# Arc.net
KiCad netlist of a schematic drawn in Altium Designer
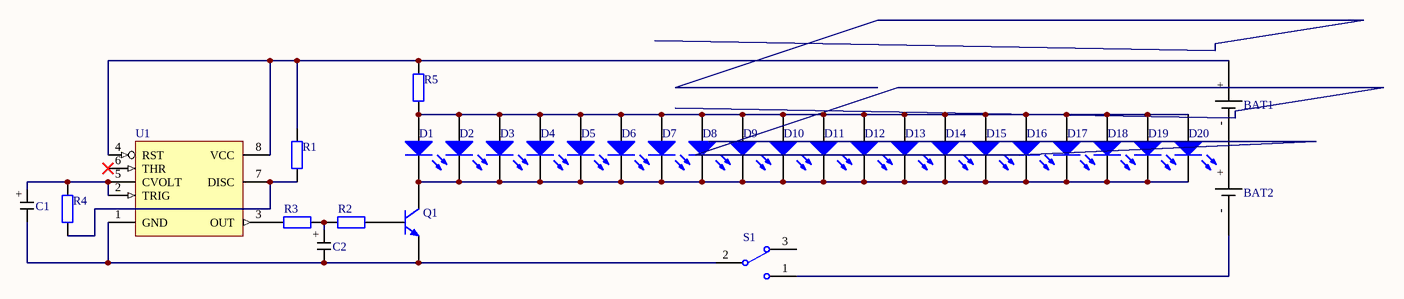
[diagram p0: Arc.SchDoc]

(export (version "E")
  (design (tool "Eeschema 10.0.6"))
  (components
    (comp (ref "BAT1") (value "Power") (footprint "CR1220_Dock") (libsource (lib "Powerlib") (part "Power")))
    (comp (ref "BAT2") (value "Power") (footprint "CR1220_Dock") (libsource (lib "Powerlib") (part "Power")))
    (comp (ref "C1") (value "Cap") (footprint "*CAPCP3528X210N") (libsource (lib "Powerlib") (part "Cap")))
    (comp (ref "C2") (value "Cap") (footprint "*CAPCP3528X210N") (libsource (lib "Powerlib") (part "Cap")))
    (comp (ref "D1")
      (value "蓝灯 0603")
      (footprint "0603_LED_S1")
      (description "发光二极管")
      (libsource (lib "Miscellaneous Devices LC") (part "0603 蓝灯"))
    )
    (comp (ref "D2")
      (value "蓝灯 0603")
      (footprint "0603_LED_S1")
      (description "发光二极管")
      (libsource (lib "Miscellaneous Devices LC") (part "0603 蓝灯"))
    )
    (comp (ref "D3")
      (value "蓝灯 0603")
      (footprint "0603_LED_S1")
      (description "发光二极管")
      (libsource (lib "Miscellaneous Devices LC") (part "0603 蓝灯"))
    )
    (comp (ref "D4")
      (value "蓝灯 0603")
      (footprint "0603_LED_S1")
      (description "发光二极管")
      (libsource (lib "Miscellaneous Devices LC") (part "0603 蓝灯"))
    )
    (comp (ref "D5")
      (value "蓝灯 0603")
      (footprint "0603_LED_S1")
      (description "发光二极管")
      (libsource (lib "Miscellaneous Devices LC") (part "0603 蓝灯"))
    )
    (comp (ref "D6")
      (value "蓝灯 0603")
      (footprint "0603_LED_S1")
      (description "发光二极管")
      (libsource (lib "Miscellaneous Devices LC") (part "0603 蓝灯"))
    )
    (comp (ref "D7")
      (value "蓝灯 0603")
      (footprint "0603_LED_S1")
      (description "发光二极管")
      (libsource (lib "Miscellaneous Devices LC") (part "0603 蓝灯"))
    )
    (comp (ref "D8")
      (value "蓝灯 0603")
      (footprint "0603_LED_S1")
      (description "发光二极管")
      (libsource (lib "Miscellaneous Devices LC") (part "0603 蓝灯"))
    )
    (comp (ref "D9")
      (value "蓝灯 0603")
      (footprint "0603_LED_S1")
      (description "发光二极管")
      (libsource (lib "Miscellaneous Devices LC") (part "0603 蓝灯"))
    )
    (comp (ref "D10")
      (value "蓝灯 0603")
      (footprint "0603_LED_S1")
      (description "发光二极管")
      (libsource (lib "Miscellaneous Devices LC") (part "0603 蓝灯"))
    )
    (comp (ref "D11")
      (value "蓝灯 0603")
      (footprint "0603_LED_S1")
      (description "发光二极管")
      (libsource (lib "Miscellaneous Devices LC") (part "0603 蓝灯"))
    )
    (comp (ref "D12")
      (value "蓝灯 0603")
      (footprint "0603_LED_S1")
      (description "发光二极管")
      (libsource (lib "Miscellaneous Devices LC") (part "0603 蓝灯"))
    )
    (comp (ref "D13")
      (value "蓝灯 0603")
      (footprint "0603_LED_S1")
      (description "发光二极管")
      (libsource (lib "Miscellaneous Devices LC") (part "0603 蓝灯"))
    )
    (comp (ref "D14")
      (value "蓝灯 0603")
      (footprint "0603_LED_S1")
      (description "发光二极管")
      (libsource (lib "Miscellaneous Devices LC") (part "0603 蓝灯"))
    )
    (comp (ref "D15")
      (value "蓝灯 0603")
      (footprint "0603_LED_S1")
      (description "发光二极管")
      (libsource (lib "Miscellaneous Devices LC") (part "0603 蓝灯"))
    )
    (comp (ref "D16")
      (value "蓝灯 0603")
      (footprint "0603_LED_S1")
      (description "发光二极管")
      (libsource (lib "Miscellaneous Devices LC") (part "0603 蓝灯"))
    )
    (comp (ref "D17")
      (value "蓝灯 0603")
      (footprint "0603_LED_S1")
      (description "发光二极管")
      (libsource (lib "Miscellaneous Devices LC") (part "0603 蓝灯"))
    )
    (comp (ref "D18")
      (value "蓝灯 0603")
      (footprint "0603_LED_S1")
      (description "发光二极管")
      (libsource (lib "Miscellaneous Devices LC") (part "0603 蓝灯"))
    )
    (comp (ref "D19")
      (value "蓝灯 0603")
      (footprint "0603_LED_S1")
      (description "发光二极管")
      (libsource (lib "Miscellaneous Devices LC") (part "0603 蓝灯"))
    )
    (comp (ref "D20")
      (value "蓝灯 0603")
      (footprint "0603_LED_S1")
      (description "发光二极管")
      (libsource (lib "Miscellaneous Devices LC") (part "0603 蓝灯"))
    )
    (comp (ref "Q1")
      (value "SS8050 Y1")
      (footprint "SOT-23(SOT-23-3)")
      (description "三极管")
      (libsource (lib "Miscellaneous Devices LC") (part "SOT-23 SS8050 Y1"))
    )
    (comp (ref "R1")
      (value "10KΩ (1002) ±1%")
      (footprint "0603_R")
      (description "贴片电阻")
      (libsource (lib "Miscellaneous Devices LC") (part "0603 10KΩ (1002) 1%"))
    )
    (comp (ref "R2")
      (value "10KΩ (1002) ±1%")
      (footprint "0603_R")
      (description "贴片电阻")
      (libsource (lib "") (part "0603 10KΩ (1002) 1%_1"))
    )
    (comp (ref "R3")
      (value "47KΩ (4702) ±1%")
      (footprint "0603_R")
      (description "贴片电阻")
      (libsource (lib "") (part "0603 47KΩ (4702) 1%_1"))
    )
    (comp (ref "R4")
      (value "47KΩ (4702) ±1%")
      (footprint "0603_R")
      (description "贴片电阻")
      (libsource (lib "Miscellaneous Devices LC") (part "0603 47KΩ (4702) 1%"))
    )
    (comp (ref "R5")
      (value "1.6k")
      (footprint "0603_R")
      (description "贴片电阻")
      (libsource (lib "Miscellaneous Devices LC") (part "0603 1.2KΩ (1201) 1%"))
    )
    (comp (ref "S1")
      (value "SW-SPDT")
      (footprint "sw_9*3.5*5.5mm")
      (description "SPDT Subminiature Toggle Switch, Right Angle Mounting, Vertical Actuation")
      (fields (field (name "PUBLISHER") "Altium Limited"))
      (libsource (lib "Miscellaneous Devices") (part "SW-SPDT"))
    )
    (comp (ref "U1")
      (value "NE555DR")
      (footprint "SOIC-8_150mil")
      (description "时基集成")
      (libsource (lib "Miscellaneous Devices LC") (part "NE555DR_[C7593]"))
    )
  )
  (nets
    (net (code "1") (name "Net-(BAT1-Pad-)") (class "Default")
      (node (ref "BAT1") (pin "-") (pinfunction "-_-") (pintype "passive"))
      (node (ref "BAT2") (pin "+") (pinfunction "+_+") (pintype "passive"))
    )
    (net (code "2") (name "Net-(BAT2-Pad-)") (class "Default")
      (node (ref "BAT2") (pin "-") (pinfunction "-_-") (pintype "passive"))
      (node (ref "S1") (pin "1") (pinfunction "1_1") (pintype "passive"))
    )
    (net (code "3") (name "Net-(C2-Pad+)") (class "Default")
      (node (ref "C2") (pin "+") (pinfunction "+_+") (pintype "passive"))
      (node (ref "R2") (pin "2") (pinfunction "2_2") (pintype "passive"))
      (node (ref "R3") (pin "2") (pinfunction "2_2") (pintype "passive"))
    )
    (net (code "4") (name "Net-(D1-PadA)") (class "Default")
      (node (ref "D1") (pin "A") (pinfunction "A_A") (pintype "passive"))
      (node (ref "D10") (pin "A") (pinfunction "A_A") (pintype "passive"))
      (node (ref "D11") (pin "A") (pinfunction "A_A") (pintype "passive"))
      (node (ref "D12") (pin "A") (pinfunction "A_A") (pintype "passive"))
      (node (ref "D13") (pin "A") (pinfunction "A_A") (pintype "passive"))
      (node (ref "D14") (pin "A") (pinfunction "A_A") (pintype "passive"))
      (node (ref "D15") (pin "A") (pinfunction "A_A") (pintype "passive"))
      (node (ref "D16") (pin "A") (pinfunction "A_A") (pintype "passive"))
      (node (ref "D17") (pin "A") (pinfunction "A_A") (pintype "passive"))
      (node (ref "D18") (pin "A") (pinfunction "A_A") (pintype "passive"))
      (node (ref "D19") (pin "A") (pinfunction "A_A") (pintype "passive"))
      (node (ref "D2") (pin "A") (pinfunction "A_A") (pintype "passive"))
      (node (ref "D20") (pin "A") (pinfunction "A_A") (pintype "passive"))
      (node (ref "D3") (pin "A") (pinfunction "A_A") (pintype "passive"))
      (node (ref "D4") (pin "A") (pinfunction "A_A") (pintype "passive"))
      (node (ref "D5") (pin "A") (pinfunction "A_A") (pintype "passive"))
      (node (ref "D6") (pin "A") (pinfunction "A_A") (pintype "passive"))
      (node (ref "D7") (pin "A") (pinfunction "A_A") (pintype "passive"))
      (node (ref "D8") (pin "A") (pinfunction "A_A") (pintype "passive"))
      (node (ref "D9") (pin "A") (pinfunction "A_A") (pintype "passive"))
      (node (ref "R5") (pin "1") (pinfunction "1_1") (pintype "passive"))
    )
    (net (code "5") (name "Net-(Q1-B)") (class "Default")
      (node (ref "Q1") (pin "1") (pinfunction "B_1") (pintype "passive"))
      (node (ref "R2") (pin "1") (pinfunction "1_1") (pintype "passive"))
    )
    (net (code "6") (name "Net-(Q1-C)") (class "Default")
      (node (ref "D1") (pin "K") (pinfunction "K_K") (pintype "passive"))
      (node (ref "D10") (pin "K") (pinfunction "K_K") (pintype "passive"))
      (node (ref "D11") (pin "K") (pinfunction "K_K") (pintype "passive"))
      (node (ref "D12") (pin "K") (pinfunction "K_K") (pintype "passive"))
      (node (ref "D13") (pin "K") (pinfunction "K_K") (pintype "passive"))
      (node (ref "D14") (pin "K") (pinfunction "K_K") (pintype "passive"))
      (node (ref "D15") (pin "K") (pinfunction "K_K") (pintype "passive"))
      (node (ref "D16") (pin "K") (pinfunction "K_K") (pintype "passive"))
      (node (ref "D17") (pin "K") (pinfunction "K_K") (pintype "passive"))
      (node (ref "D18") (pin "K") (pinfunction "K_K") (pintype "passive"))
      (node (ref "D19") (pin "K") (pinfunction "K_K") (pintype "passive"))
      (node (ref "D2") (pin "K") (pinfunction "K_K") (pintype "passive"))
      (node (ref "D20") (pin "K") (pinfunction "K_K") (pintype "passive"))
      (node (ref "D3") (pin "K") (pinfunction "K_K") (pintype "passive"))
      (node (ref "D4") (pin "K") (pinfunction "K_K") (pintype "passive"))
      (node (ref "D5") (pin "K") (pinfunction "K_K") (pintype "passive"))
      (node (ref "D6") (pin "K") (pinfunction "K_K") (pintype "passive"))
      (node (ref "D7") (pin "K") (pinfunction "K_K") (pintype "passive"))
      (node (ref "D8") (pin "K") (pinfunction "K_K") (pintype "passive"))
      (node (ref "D9") (pin "K") (pinfunction "K_K") (pintype "passive"))
      (node (ref "Q1") (pin "3") (pinfunction "C_3") (pintype "passive"))
    )
    (net (code "7") (name "Net-(Q1-E)") (class "Default")
      (node (ref "C1") (pin "_") (pinfunction "___") (pintype "passive"))
      (node (ref "C2") (pin "_") (pinfunction "___") (pintype "passive"))
      (node (ref "Q1") (pin "2") (pinfunction "E_2") (pintype "passive"))
      (node (ref "S1") (pin "2") (pinfunction "2_2") (pintype "passive"))
      (node (ref "U1") (pin "1") (pinfunction "GND_1") (pintype "power_in"))
    )
    (net (code "8") (name "Net-(U1-CVOLT)") (class "Default")
      (node (ref "C1") (pin "+") (pinfunction "+_+") (pintype "passive"))
      (node (ref "R4") (pin "2") (pinfunction "2_2") (pintype "passive"))
      (node (ref "U1") (pin "2") (pinfunction "TRIG_2") (pintype "input"))
      (node (ref "U1") (pin "5") (pinfunction "CVOLT_5") (pintype "passive"))
    )
    (net (code "9") (name "Net-(U1-DISC)") (class "Default")
      (node (ref "R1") (pin "1") (pinfunction "1_1") (pintype "passive"))
      (node (ref "R4") (pin "1") (pinfunction "1_1") (pintype "passive"))
      (node (ref "U1") (pin "7") (pinfunction "DISC_7") (pintype "open_collector"))
    )
    (net (code "10") (name "Net-(U1-OUT)") (class "Default")
      (node (ref "R3") (pin "1") (pinfunction "1_1") (pintype "passive"))
      (node (ref "U1") (pin "3") (pinfunction "OUT_3") (pintype "output"))
    )
    (net (code "11") (name "Net-(U1-RST)") (class "Default")
      (node (ref "BAT1") (pin "+") (pinfunction "+_+") (pintype "passive"))
      (node (ref "R1") (pin "2") (pinfunction "2_2") (pintype "passive"))
      (node (ref "R5") (pin "2") (pinfunction "2_2") (pintype "passive"))
      (node (ref "U1") (pin "4") (pinfunction "RST_4") (pintype "input"))
      (node (ref "U1") (pin "8") (pinfunction "VCC_8") (pintype "power_in"))
    )
    (net (code "12") (name "unconnected-(S1-Pad3)") (class "Default")
      (node (ref "S1") (pin "3") (pinfunction "3_3") (pintype "passive"))
    )
    (net (code "13") (name "unconnected-(U1-THR-Pad6)") (class "Default")
      (node (ref "U1") (pin "6") (pinfunction "THR_6") (pintype "input+no_connect"))
    )
  )
)
